# arduino_rx.net
KiCad netlist of a schematic drawn in EAGLE
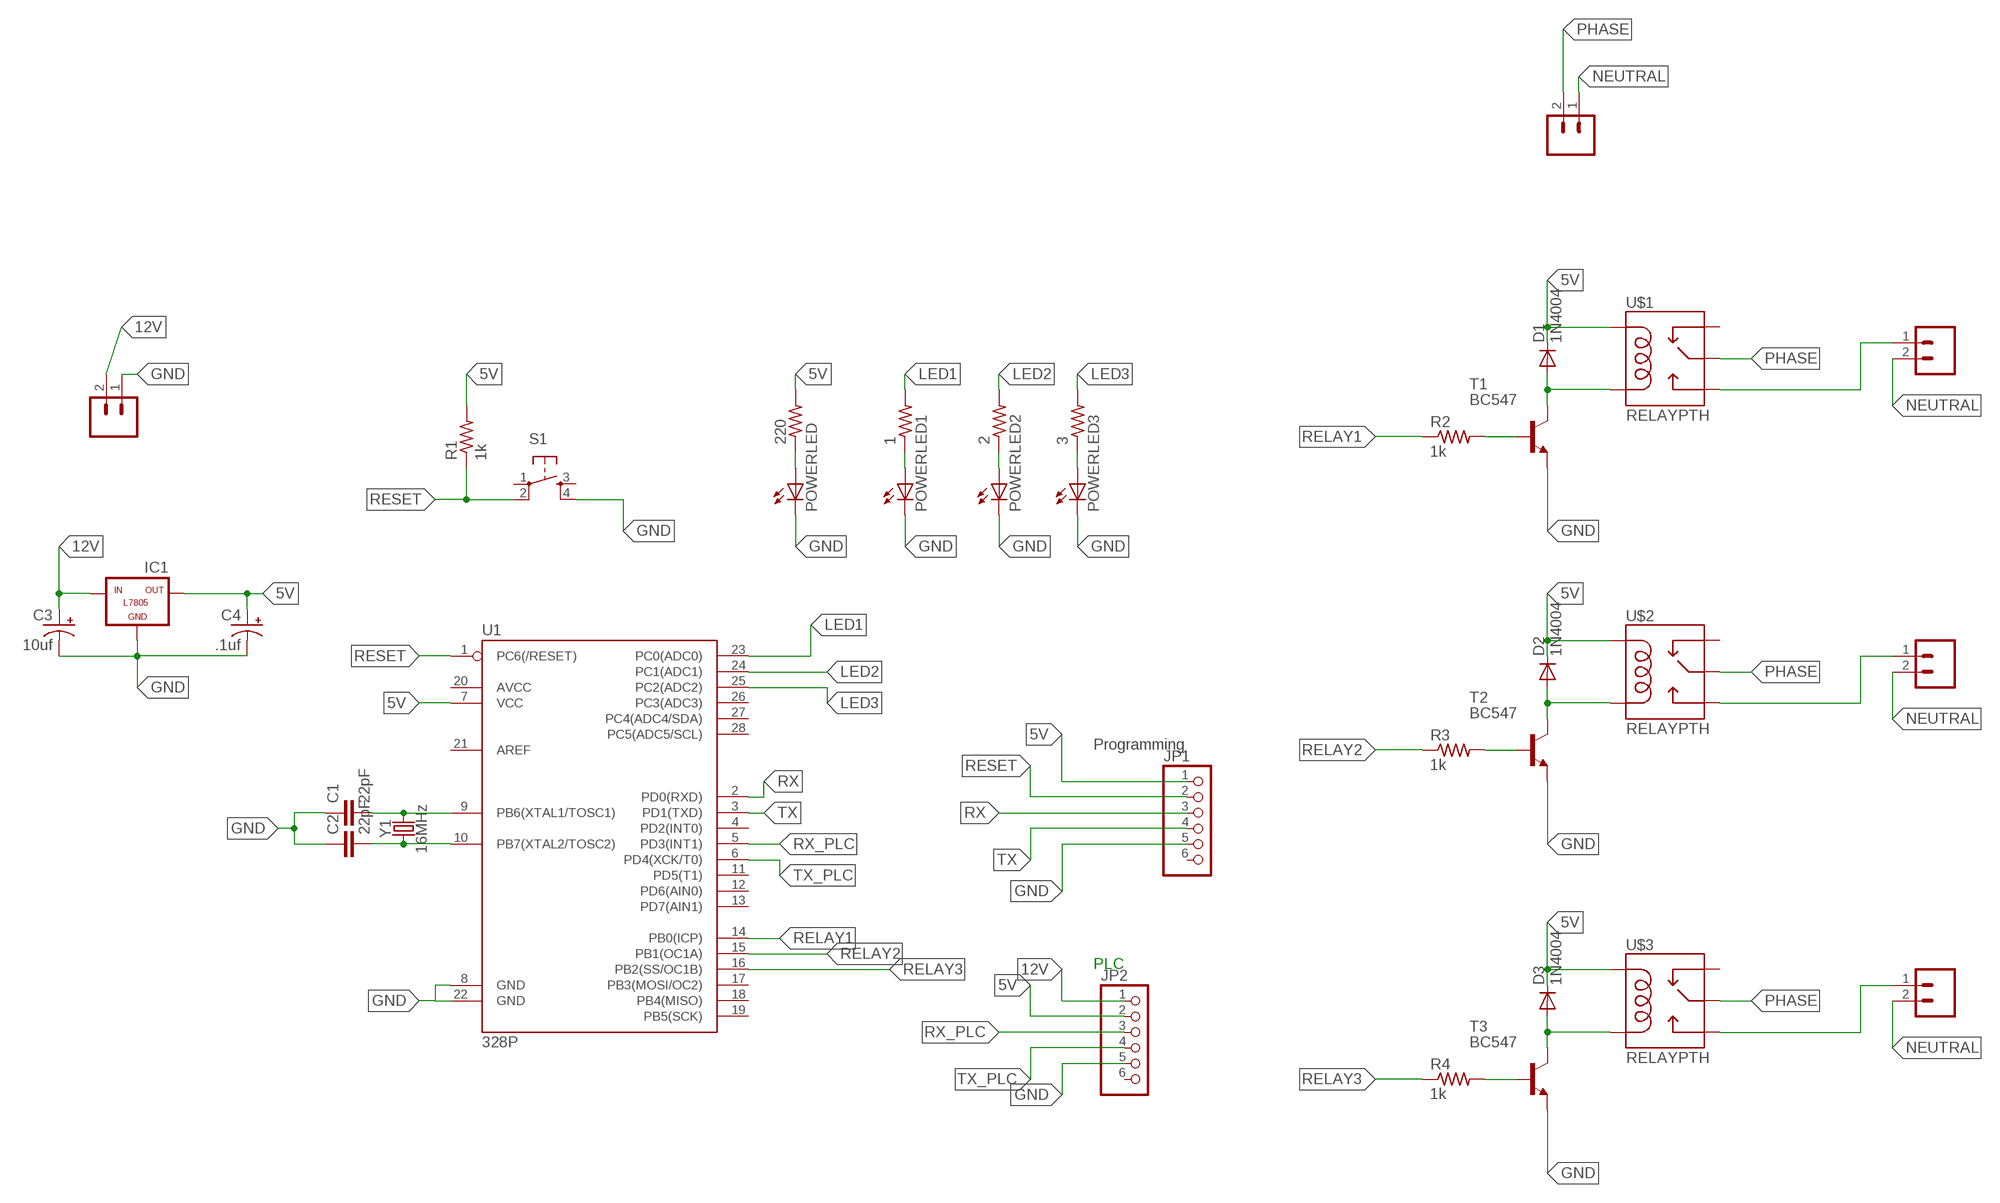
[diagram p0: schematic, sheet 1]

(export (version "E")
  (design (tool "Eeschema 10.0.6"))
  (components
    (comp (ref "1")
      (value "R-US_0204/5")
      (footprint "eagle-import:0204_5")
      (libsource (lib "eagle-import") (part "R-US_0204/5"))
    )
    (comp (ref "2")
      (value "R-US_0204/5")
      (footprint "eagle-import:0204_5")
      (libsource (lib "eagle-import") (part "R-US_0204/5"))
    )
    (comp (ref "3")
      (value "R-US_0204/5")
      (footprint "eagle-import:0204_5")
      (libsource (lib "eagle-import") (part "R-US_0204/5"))
    )
    (comp (ref "220")
      (value "R-US_0204/5")
      (footprint "eagle-import:0204_5")
      (libsource (lib "eagle-import") (part "R-US_0204/5"))
    )
    (comp (ref "C1")
      (value "22pF")
      (footprint "eagle-import:CAP-PTH-2.54")
      (libsource (lib "eagle-import") (part "22PF-PTH-2.54MM-200V-5%"))
    )
    (comp (ref "C2")
      (value "22pF")
      (footprint "eagle-import:CAP-PTH-2.54")
      (libsource (lib "eagle-import") (part "22PF-PTH-2.54MM-200V-5%"))
    )
    (comp (ref "C3")
      (value "10uf")
      (footprint "eagle-import:E5-5")
      (libsource (lib "eagle-import") (part "CPOL-USE5-5"))
    )
    (comp (ref "C4")
      (value ".1uf")
      (footprint "eagle-import:E5-5")
      (libsource (lib "eagle-import") (part "CPOL-USE5-5"))
    )
    (comp (ref "D1")
      (value "1N4004")
      (footprint "eagle-import:DO41-10")
      (libsource (lib "eagle-import") (part "1N4004"))
    )
    (comp (ref "D2")
      (value "1N4004")
      (footprint "eagle-import:DO41-10")
      (libsource (lib "eagle-import") (part "1N4004"))
    )
    (comp (ref "D3")
      (value "1N4004")
      (footprint "eagle-import:DO41-10")
      (libsource (lib "eagle-import") (part "1N4004"))
    )
    (comp (ref "IC1")
      (value "L7805")
      (footprint "eagle-import:78XXL")
      (libsource (lib "eagle-import") (part "L7805"))
    )
    (comp (ref "J1")
      (value "CONN_023.5MM")
      (footprint "eagle-import:SCREWTERMINAL-3.5MM-2")
      (libsource (lib "eagle-import") (part "CONN_023.5MM"))
    )
    (comp (ref "J2")
      (value "CONN_023.5MM")
      (footprint "eagle-import:SCREWTERMINAL-3.5MM-2")
      (libsource (lib "eagle-import") (part "CONN_023.5MM"))
    )
    (comp (ref "J4")
      (value "CONN_023.5MM")
      (footprint "eagle-import:SCREWTERMINAL-3.5MM-2")
      (libsource (lib "eagle-import") (part "CONN_023.5MM"))
    )
    (comp (ref "J5")
      (value "CONN_023.5MM")
      (footprint "eagle-import:SCREWTERMINAL-3.5MM-2")
      (libsource (lib "eagle-import") (part "CONN_023.5MM"))
    )
    (comp (ref "J6")
      (value "CONN_023.5MM")
      (footprint "eagle-import:SCREWTERMINAL-3.5MM-2")
      (libsource (lib "eagle-import") (part "CONN_023.5MM"))
    )
    (comp (ref "JP1")
      (value "PINHD-1X6")
      (footprint "eagle-import:1X06")
      (libsource (lib "eagle-import") (part "PINHD-1X6"))
    )
    (comp (ref "JP2")
      (value "PINHD-1X6")
      (footprint "eagle-import:1X06")
      (libsource (lib "eagle-import") (part "PINHD-1X6"))
    )
    (comp (ref "POWERLED")
      (value "LED5MM")
      (footprint "eagle-import:LED5MM")
      (libsource (lib "eagle-import") (part "LED5MM"))
    )
    (comp (ref "POWERLED1")
      (value "LED5MM")
      (footprint "eagle-import:LED5MM")
      (libsource (lib "eagle-import") (part "LED5MM"))
    )
    (comp (ref "POWERLED2")
      (value "LED5MM")
      (footprint "eagle-import:LED5MM")
      (libsource (lib "eagle-import") (part "LED5MM"))
    )
    (comp (ref "POWERLED3")
      (value "LED5MM")
      (footprint "eagle-import:LED5MM")
      (libsource (lib "eagle-import") (part "LED5MM"))
    )
    (comp (ref "R1")
      (value "1k")
      (footprint "eagle-import:0204_5")
      (libsource (lib "eagle-import") (part "R-US_0204/5"))
    )
    (comp (ref "R2")
      (value "1k")
      (footprint "eagle-import:0204_5")
      (libsource (lib "eagle-import") (part "R-US_0204/5"))
    )
    (comp (ref "R3")
      (value "1k")
      (footprint "eagle-import:0204_5")
      (libsource (lib "eagle-import") (part "R-US_0204/5"))
    )
    (comp (ref "R4")
      (value "1k")
      (footprint "eagle-import:0204_5")
      (libsource (lib "eagle-import") (part "R-US_0204/5"))
    )
    (comp (ref "S1")
      (value "TAC_SWITCHPTH")
      (footprint "eagle-import:TACTILE-PTH")
      (libsource (lib "eagle-import") (part "TAC_SWITCHPTH"))
    )
    (comp (ref "T1")
      (value "BC547")
      (footprint "eagle-import:TO92")
      (libsource (lib "eagle-import") (part "BC547"))
    )
    (comp (ref "T2")
      (value "BC547")
      (footprint "eagle-import:TO92")
      (libsource (lib "eagle-import") (part "BC547"))
    )
    (comp (ref "T3")
      (value "BC547")
      (footprint "eagle-import:TO92")
      (libsource (lib "eagle-import") (part "BC547"))
    )
    (comp (ref "U$1")
      (value "RELAYPTH")
      (footprint "eagle-import:SRD-05VDC-SL-C")
      (libsource (lib "eagle-import") (part "RELAYPTH"))
    )
    (comp (ref "U$2")
      (value "RELAYPTH")
      (footprint "eagle-import:SRD-05VDC-SL-C")
      (libsource (lib "eagle-import") (part "RELAYPTH"))
    )
    (comp (ref "U$3")
      (value "RELAYPTH")
      (footprint "eagle-import:SRD-05VDC-SL-C")
      (libsource (lib "eagle-import") (part "RELAYPTH"))
    )
    (comp (ref "U1")
      (value "328P")
      (footprint "eagle-import:DIP28")
      (libsource (lib "eagle-import") (part "ATMEGA328P_PDIP"))
    )
    (comp (ref "Y1")
      (value "16MHz")
      (footprint "eagle-import:HC49US")
      (libsource (lib "eagle-import") (part "CRYSTAL-16MHZPTH-HC49US"))
    )
  )
  (nets
    (net (code "1") (name "5V") (class "Default")
      (node (ref "220") (pin "2") (pinfunction "2_2") (pintype "passive"))
      (node (ref "C4") (pin "+") (pinfunction "+_+") (pintype "passive"))
      (node (ref "D1") (pin "C") (pinfunction "C_C") (pintype "passive"))
      (node (ref "D2") (pin "C") (pinfunction "C_C") (pintype "passive"))
      (node (ref "D3") (pin "C") (pinfunction "C_C") (pintype "passive"))
      (node (ref "IC1") (pin "OUT") (pinfunction "OUT_OUT") (pintype "passive"))
      (node (ref "JP1") (pin "1") (pinfunction "1_1") (pintype "passive"))
      (node (ref "JP2") (pin "2") (pinfunction "2_2") (pintype "passive"))
      (node (ref "R1") (pin "2") (pinfunction "2_2") (pintype "passive"))
      (node (ref "U$1") (pin "COIL1") (pinfunction "COIL1_COIL1") (pintype "bidirectional"))
      (node (ref "U$2") (pin "COIL1") (pinfunction "COIL1_COIL1") (pintype "bidirectional"))
      (node (ref "U$3") (pin "COIL1") (pinfunction "COIL1_COIL1") (pintype "bidirectional"))
      (node (ref "U1") (pin "7") (pinfunction "VCC_7") (pintype "bidirectional"))
    )
    (net (code "2") (name "12V") (class "Default")
      (node (ref "C3") (pin "+") (pinfunction "+_+") (pintype "passive"))
      (node (ref "IC1") (pin "IN") (pinfunction "IN_IN") (pintype "input"))
      (node (ref "J1") (pin "2") (pinfunction "2_2") (pintype "passive"))
      (node (ref "JP2") (pin "1") (pinfunction "1_1") (pintype "passive"))
    )
    (net (code "3") (name "GND") (class "Default")
      (node (ref "C1") (pin "1") (pinfunction "1_1") (pintype "passive"))
      (node (ref "C2") (pin "1") (pinfunction "1_1") (pintype "passive"))
      (node (ref "C3") (pin "-") (pinfunction "-_-") (pintype "passive"))
      (node (ref "C4") (pin "-") (pinfunction "-_-") (pintype "passive"))
      (node (ref "IC1") (pin "GND") (pinfunction "GND_GND") (pintype "input"))
      (node (ref "J1") (pin "1") (pinfunction "1_1") (pintype "passive"))
      (node (ref "JP1") (pin "5") (pinfunction "5_5") (pintype "passive"))
      (node (ref "JP2") (pin "5") (pinfunction "5_5") (pintype "passive"))
      (node (ref "POWERLED") (pin "K") (pinfunction "C_K") (pintype "passive"))
      (node (ref "POWERLED1") (pin "K") (pinfunction "C_K") (pintype "passive"))
      (node (ref "POWERLED2") (pin "K") (pinfunction "C_K") (pintype "passive"))
      (node (ref "POWERLED3") (pin "K") (pinfunction "C_K") (pintype "passive"))
      (node (ref "S1") (pin "4") (pinfunction "4_4") (pintype "passive"))
      (node (ref "T1") (pin "1") (pinfunction "E_1") (pintype "passive"))
      (node (ref "T2") (pin "1") (pinfunction "E_1") (pintype "passive"))
      (node (ref "T3") (pin "1") (pinfunction "E_1") (pintype "passive"))
      (node (ref "U1") (pin "22") (pinfunction "GND_22") (pintype "bidirectional"))
      (node (ref "U1") (pin "8") (pinfunction "GND_8") (pintype "bidirectional"))
    )
    (net (code "4") (name "LED1") (class "Default")
      (node (ref "1") (pin "2") (pinfunction "2_2") (pintype "passive"))
      (node (ref "U1") (pin "23") (pinfunction "PC0(ADC0)_23") (pintype "bidirectional"))
    )
    (net (code "5") (name "LED2") (class "Default")
      (node (ref "2") (pin "2") (pinfunction "2_2") (pintype "passive"))
      (node (ref "U1") (pin "24") (pinfunction "PC1(ADC1)_24") (pintype "bidirectional"))
    )
    (net (code "6") (name "LED3") (class "Default")
      (node (ref "3") (pin "2") (pinfunction "2_2") (pintype "passive"))
      (node (ref "U1") (pin "25") (pinfunction "PC2(ADC2)_25") (pintype "bidirectional"))
    )
    (net (code "7") (name "NEUTRAL") (class "Default")
      (node (ref "J2") (pin "1") (pinfunction "1_1") (pintype "passive"))
      (node (ref "J4") (pin "2") (pinfunction "2_2") (pintype "passive"))
      (node (ref "J5") (pin "2") (pinfunction "2_2") (pintype "passive"))
      (node (ref "J6") (pin "2") (pinfunction "2_2") (pintype "passive"))
    )
    (net (code "8") (name "Net-(1-Pad1)") (class "Default")
      (node (ref "1") (pin "1") (pinfunction "1_1") (pintype "passive"))
      (node (ref "POWERLED1") (pin "A") (pinfunction "A_A") (pintype "passive"))
    )
    (net (code "9") (name "Net-(2-Pad1)") (class "Default")
      (node (ref "2") (pin "1") (pinfunction "1_1") (pintype "passive"))
      (node (ref "POWERLED2") (pin "A") (pinfunction "A_A") (pintype "passive"))
    )
    (net (code "10") (name "Net-(3-Pad1)") (class "Default")
      (node (ref "3") (pin "1") (pinfunction "1_1") (pintype "passive"))
      (node (ref "POWERLED3") (pin "A") (pinfunction "A_A") (pintype "passive"))
    )
    (net (code "11") (name "Net-(220-Pad1)") (class "Default")
      (node (ref "220") (pin "1") (pinfunction "1_1") (pintype "passive"))
      (node (ref "POWERLED") (pin "A") (pinfunction "A_A") (pintype "passive"))
    )
    (net (code "12") (name "Net-(J4-Pad1)") (class "Default")
      (node (ref "J4") (pin "1") (pinfunction "1_1") (pintype "passive"))
      (node (ref "U$1") (pin "SWOPEN") (pinfunction "SWOPEN_SWOPEN") (pintype "bidirectional"))
    )
    (net (code "13") (name "Net-(J5-Pad1)") (class "Default")
      (node (ref "J5") (pin "1") (pinfunction "1_1") (pintype "passive"))
      (node (ref "U$2") (pin "SWOPEN") (pinfunction "SWOPEN_SWOPEN") (pintype "bidirectional"))
    )
    (net (code "14") (name "Net-(J6-Pad1)") (class "Default")
      (node (ref "J6") (pin "1") (pinfunction "1_1") (pintype "passive"))
      (node (ref "U$3") (pin "SWOPEN") (pinfunction "SWOPEN_SWOPEN") (pintype "bidirectional"))
    )
    (net (code "15") (name "Net-(T1-B)") (class "Default")
      (node (ref "R2") (pin "2") (pinfunction "2_2") (pintype "passive"))
      (node (ref "T1") (pin "2") (pinfunction "B_2") (pintype "passive"))
    )
    (net (code "16") (name "Net-(T1-C)") (class "Default")
      (node (ref "D1") (pin "A") (pinfunction "A_A") (pintype "passive"))
      (node (ref "T1") (pin "3") (pinfunction "C_3") (pintype "passive"))
      (node (ref "U$1") (pin "COIL0") (pinfunction "COIL0_COIL0") (pintype "bidirectional"))
    )
    (net (code "17") (name "Net-(T2-B)") (class "Default")
      (node (ref "R3") (pin "2") (pinfunction "2_2") (pintype "passive"))
      (node (ref "T2") (pin "2") (pinfunction "B_2") (pintype "passive"))
    )
    (net (code "18") (name "Net-(T2-C)") (class "Default")
      (node (ref "D2") (pin "A") (pinfunction "A_A") (pintype "passive"))
      (node (ref "T2") (pin "3") (pinfunction "C_3") (pintype "passive"))
      (node (ref "U$2") (pin "COIL0") (pinfunction "COIL0_COIL0") (pintype "bidirectional"))
    )
    (net (code "19") (name "Net-(T3-B)") (class "Default")
      (node (ref "R4") (pin "2") (pinfunction "2_2") (pintype "passive"))
      (node (ref "T3") (pin "2") (pinfunction "B_2") (pintype "passive"))
    )
    (net (code "20") (name "Net-(T3-C)") (class "Default")
      (node (ref "D3") (pin "A") (pinfunction "A_A") (pintype "passive"))
      (node (ref "T3") (pin "3") (pinfunction "C_3") (pintype "passive"))
      (node (ref "U$3") (pin "COIL0") (pinfunction "COIL0_COIL0") (pintype "bidirectional"))
    )
    (net (code "21") (name "Net-(U1-PB6(XTAL1{slash}TOSC1))") (class "Default")
      (node (ref "C1") (pin "2") (pinfunction "2_2") (pintype "passive"))
      (node (ref "U1") (pin "9") (pinfunction "PB6(XTAL1/TOSC1)_9") (pintype "bidirectional"))
      (node (ref "Y1") (pin "2") (pinfunction "2_2") (pintype "passive"))
    )
    (net (code "22") (name "Net-(U1-PB7(XTAL2{slash}TOSC2))") (class "Default")
      (node (ref "C2") (pin "2") (pinfunction "2_2") (pintype "passive"))
      (node (ref "U1") (pin "10") (pinfunction "PB7(XTAL2/TOSC2)_10") (pintype "bidirectional"))
      (node (ref "Y1") (pin "1") (pinfunction "1_1") (pintype "passive"))
    )
    (net (code "23") (name "PHASE") (class "Default")
      (node (ref "J2") (pin "2") (pinfunction "2_2") (pintype "passive"))
      (node (ref "U$1") (pin "SWCOMMON") (pinfunction "SWCOMMON_SWCOMMON") (pintype "bidirectional"))
      (node (ref "U$2") (pin "SWCOMMON") (pinfunction "SWCOMMON_SWCOMMON") (pintype "bidirectional"))
      (node (ref "U$3") (pin "SWCOMMON") (pinfunction "SWCOMMON_SWCOMMON") (pintype "bidirectional"))
    )
    (net (code "24") (name "RELAY1") (class "Default")
      (node (ref "R2") (pin "1") (pinfunction "1_1") (pintype "passive"))
      (node (ref "U1") (pin "14") (pinfunction "PB0(ICP)_14") (pintype "bidirectional"))
    )
    (net (code "25") (name "RELAY2") (class "Default")
      (node (ref "R3") (pin "1") (pinfunction "1_1") (pintype "passive"))
      (node (ref "U1") (pin "15") (pinfunction "PB1(OC1A)_15") (pintype "bidirectional"))
    )
    (net (code "26") (name "RELAY3") (class "Default")
      (node (ref "R4") (pin "1") (pinfunction "1_1") (pintype "passive"))
      (node (ref "U1") (pin "16") (pinfunction "PB2(SS/OC1B)_16") (pintype "bidirectional"))
    )
    (net (code "27") (name "RESET") (class "Default")
      (node (ref "JP1") (pin "2") (pinfunction "2_2") (pintype "passive"))
      (node (ref "R1") (pin "1") (pinfunction "1_1") (pintype "passive"))
      (node (ref "S1") (pin "2") (pinfunction "2_2") (pintype "passive"))
      (node (ref "U1") (pin "1") (pinfunction "PC6(/RESET)_1") (pintype "bidirectional"))
    )
    (net (code "28") (name "RX") (class "Default")
      (node (ref "JP1") (pin "3") (pinfunction "3_3") (pintype "passive"))
      (node (ref "U1") (pin "2") (pinfunction "PD0(RXD)_2") (pintype "bidirectional"))
    )
    (net (code "29") (name "RX_PLC") (class "Default")
      (node (ref "JP2") (pin "3") (pinfunction "3_3") (pintype "passive"))
      (node (ref "U1") (pin "5") (pinfunction "PD3(INT1)_5") (pintype "bidirectional"))
    )
    (net (code "30") (name "TX") (class "Default")
      (node (ref "JP1") (pin "4") (pinfunction "4_4") (pintype "passive"))
      (node (ref "U1") (pin "3") (pinfunction "PD1(TXD)_3") (pintype "bidirectional"))
    )
    (net (code "31") (name "TX_PLC") (class "Default")
      (node (ref "JP2") (pin "4") (pinfunction "4_4") (pintype "passive"))
      (node (ref "U1") (pin "6") (pinfunction "PD4(XCK/T0)_6") (pintype "bidirectional"))
    )
    (net (code "32") (name "unconnected-(JP1-Pad6)") (class "Default")
      (node (ref "JP1") (pin "6") (pinfunction "6_6") (pintype "passive"))
    )
    (net (code "33") (name "unconnected-(JP2-Pad6)") (class "Default")
      (node (ref "JP2") (pin "6") (pinfunction "6_6") (pintype "passive"))
    )
    (net (code "34") (name "unconnected-(S1-Pad1)") (class "Default")
      (node (ref "S1") (pin "1") (pinfunction "1_1") (pintype "passive"))
    )
    (net (code "35") (name "unconnected-(S1-Pad3)") (class "Default")
      (node (ref "S1") (pin "3") (pinfunction "3_3") (pintype "passive"))
    )
    (net (code "36") (name "unconnected-(U$1-SWCLOSE-PadSWCLOSED)") (class "Default")
      (node (ref "U$1") (pin "SWCLOSED") (pinfunction "SWCLOSE_SWCLOSED") (pintype "bidirectional"))
    )
    (net (code "37") (name "unconnected-(U$2-SWCLOSE-PadSWCLOSED)") (class "Default")
      (node (ref "U$2") (pin "SWCLOSED") (pinfunction "SWCLOSE_SWCLOSED") (pintype "bidirectional"))
    )
    (net (code "38") (name "unconnected-(U$3-SWCLOSE-PadSWCLOSED)") (class "Default")
      (node (ref "U$3") (pin "SWCLOSED") (pinfunction "SWCLOSE_SWCLOSED") (pintype "bidirectional"))
    )
    (net (code "39") (name "unconnected-(U1-AREF-Pad21)") (class "Default")
      (node (ref "U1") (pin "21") (pinfunction "AREF_21") (pintype "bidirectional"))
    )
    (net (code "40") (name "unconnected-(U1-AVCC-Pad20)") (class "Default")
      (node (ref "U1") (pin "20") (pinfunction "AVCC_20") (pintype "bidirectional"))
    )
    (net (code "41") (name "unconnected-(U1-PB3(MOSI{slash}OC2)-Pad17)") (class "Default")
      (node (ref "U1") (pin "17") (pinfunction "PB3(MOSI/OC2)_17") (pintype "bidirectional"))
    )
    (net (code "42") (name "unconnected-(U1-PB4(MISO)-Pad18)") (class "Default")
      (node (ref "U1") (pin "18") (pinfunction "PB4(MISO)_18") (pintype "bidirectional"))
    )
    (net (code "43") (name "unconnected-(U1-PB5(SCK)-Pad19)") (class "Default")
      (node (ref "U1") (pin "19") (pinfunction "PB5(SCK)_19") (pintype "bidirectional"))
    )
    (net (code "44") (name "unconnected-(U1-PC3(ADC3)-Pad26)") (class "Default")
      (node (ref "U1") (pin "26") (pinfunction "PC3(ADC3)_26") (pintype "bidirectional"))
    )
    (net (code "45") (name "unconnected-(U1-PC4(ADC4{slash}SDA)-Pad27)") (class "Default")
      (node (ref "U1") (pin "27") (pinfunction "PC4(ADC4/SDA)_27") (pintype "bidirectional"))
    )
    (net (code "46") (name "unconnected-(U1-PC5(ADC5{slash}SCL)-Pad28)") (class "Default")
      (node (ref "U1") (pin "28") (pinfunction "PC5(ADC5/SCL)_28") (pintype "bidirectional"))
    )
    (net (code "47") (name "unconnected-(U1-PD2(INT0)-Pad4)") (class "Default")
      (node (ref "U1") (pin "4") (pinfunction "PD2(INT0)_4") (pintype "bidirectional"))
    )
    (net (code "48") (name "unconnected-(U1-PD5(T1)-Pad11)") (class "Default")
      (node (ref "U1") (pin "11") (pinfunction "PD5(T1)_11") (pintype "bidirectional"))
    )
    (net (code "49") (name "unconnected-(U1-PD6(AIN0)-Pad12)") (class "Default")
      (node (ref "U1") (pin "12") (pinfunction "PD6(AIN0)_12") (pintype "bidirectional"))
    )
    (net (code "50") (name "unconnected-(U1-PD7(AIN1)-Pad13)") (class "Default")
      (node (ref "U1") (pin "13") (pinfunction "PD7(AIN1)_13") (pintype "bidirectional"))
    )
  )
)
